# ul_tx_ctrl.net
KiCad netlist of a schematic drawn in Altium Designer
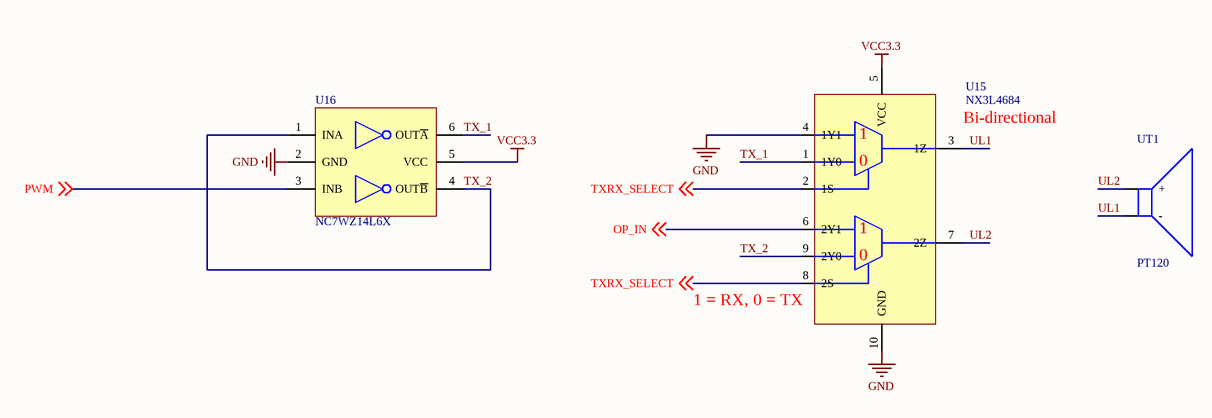
[diagram p0: ul_tx_ctrl.SchDoc]

(export (version "E")
  (design (tool "Eeschema 10.0.6"))
  (components
    (comp (ref "U15")
      (value "NX3L4684")
      (footprint "QFN50P155X200X13-10N")
      (description "IC ANALOG SWITCH SPDT 10XQFN")
      (libsource (lib "opo") (part "NX3L4684"))
    )
    (comp (ref "U16")
      (value "NC7WZ14L6X")
      (footprint "NC7WZ14L6X")
      (description "1 uA supply current, 50 mA output current, Dual inverter")
      (fields (field (name "MFR") "Fairchild Semiconductor"))
      (libsource (lib "opo_general") (part "NC7WZ14L6X"))
    )
    (comp (ref "UT1")
      (value "PT120")
      (footprint "PT120")
      (description "Ultrasonic piezoelectric transceiver, 40 khz,")
      (libsource (lib "opo_general") (part "PT120"))
    )
  )
  (nets
    (net (code "1") (name "/TX_1") (class "Default")
      (node (ref "U15") (pin "1") (pinfunction "1Y0_1") (pintype "passive"))
      (node (ref "U16") (pin "6") (pinfunction "OUT~{A}_6") (pintype "passive"))
    )
    (net (code "2") (name "/TX_2") (class "Default")
      (node (ref "U15") (pin "9") (pinfunction "2Y0_9") (pintype "passive"))
      (node (ref "U16") (pin "1") (pinfunction "INA_1") (pintype "passive"))
      (node (ref "U16") (pin "4") (pinfunction "OUT~{B}_4") (pintype "passive"))
    )
    (net (code "3") (name "/UL1") (class "Default")
      (node (ref "U15") (pin "3") (pinfunction "1Z_3") (pintype "passive"))
      (node (ref "UT1") (pin "1") (pinfunction "-_1") (pintype "passive"))
    )
    (net (code "4") (name "/UL2") (class "Default")
      (node (ref "U15") (pin "7") (pinfunction "2Z_7") (pintype "passive"))
      (node (ref "UT1") (pin "2") (pinfunction "+_2") (pintype "passive"))
    )
    (net (code "5") (name "GND") (class "Default")
      (node (ref "U15") (pin "10") (pinfunction "GND_10") (pintype "passive"))
      (node (ref "U15") (pin "4") (pinfunction "1Y1_4") (pintype "passive"))
      (node (ref "U16") (pin "2") (pinfunction "GND_2") (pintype "passive"))
    )
    (net (code "6") (name "OP_IN") (class "Default")
      (node (ref "U15") (pin "6") (pinfunction "2Y1_6") (pintype "passive"))
    )
    (net (code "7") (name "PWM") (class "Default")
      (node (ref "U16") (pin "3") (pinfunction "INB_3") (pintype "passive"))
    )
    (net (code "8") (name "TXRX_SELECT") (class "Default")
      (node (ref "U15") (pin "2") (pinfunction "1S_2") (pintype "passive"))
      (node (ref "U15") (pin "8") (pinfunction "2S_8") (pintype "passive"))
    )
    (net (code "9") (name "VCC3.3") (class "Default")
      (node (ref "U15") (pin "5") (pinfunction "VCC_5") (pintype "passive"))
      (node (ref "U16") (pin "5") (pinfunction "VCC_5") (pintype "passive"))
    )
  )
)
